# MocKhoaLedTraiTim.net
KiCad netlist of a schematic drawn in Altium Designer
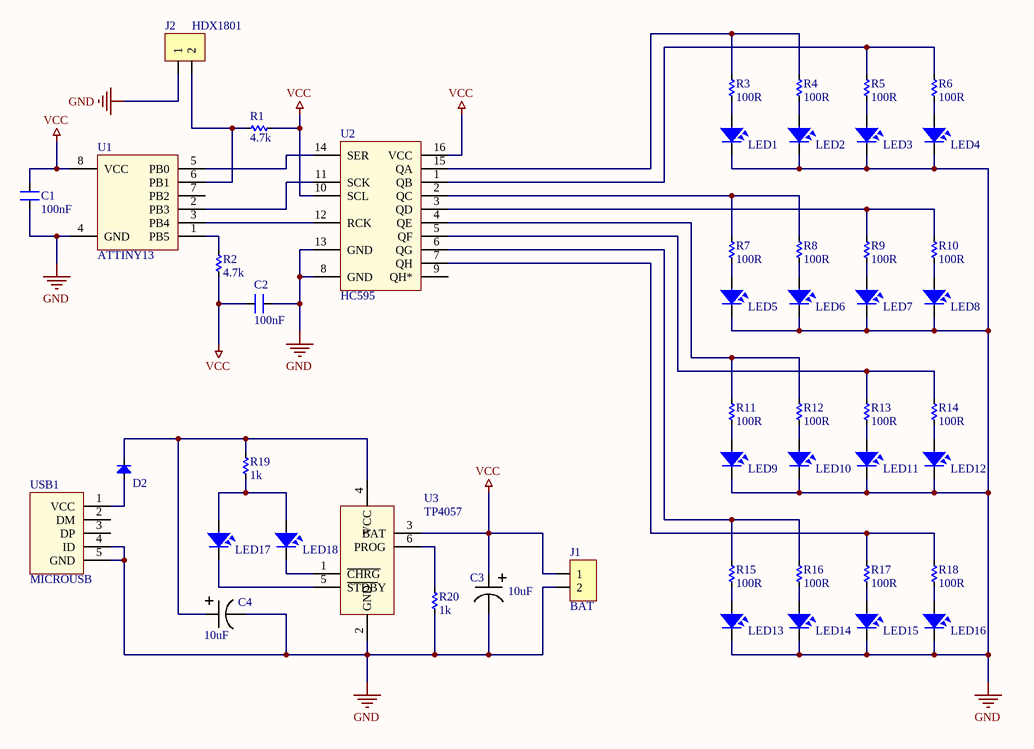
[diagram p0: MocKhoaLedTraiTim.SchDoc]

(export (version "E")
  (design (tool "Eeschema 10.0.6"))
  (components
    (comp (ref "C1") (value "100nF") (footprint "CN-SMD-0805") (libsource (lib "LIBRARY") (part "CN")))
    (comp (ref "C2") (value "100nF") (footprint "CN-SMD-0805") (libsource (lib "LIBRARY") (part "CN")))
    (comp (ref "C3") (value "10uF") (footprint "CAP1411") (libsource (lib "User") (part "CAP-TANTALUM")))
    (comp (ref "C4") (value "10uF") (footprint "CAP1411") (libsource (lib "") (part "CAP-TANTALUM_1")))
    (comp (ref "D2")
      (value "Diode SMD")
      (footprint "DIO-SMD-123")
      (description "Default Diode")
      (fields (field (name "PUBLISHER") "Altium Limited"))
      (libsource (lib "LIBRARY") (part "Diode SMD"))
    )
    (comp (ref "J1")
      (value "BAT")
      (footprint "JP2-D1T")
      (description "WR-PHD 2.54 mm Angled Socket Header")
      (fields
        (field (name "MANUFACTURER") "Würth Elektronik eiSos GmbH")
        (field (name "PARTNO") "613002143121")
        (field (name "CREATED BY") "Karrer Zheng")
      )
      (libsource (lib "LIBRARY") (part "JP2"))
    )
    (comp (ref "J2")
      (value "HDX1801")
      (footprint "JP2-D1T")
      (description "WR-PHD 2.54 mm Angled Socket Header")
      (fields
        (field (name "MANUFACTURER") "Würth Elektronik eiSos GmbH")
        (field (name "PARTNO") "613002143121")
        (field (name "CREATED BY") "Karrer Zheng")
      )
      (libsource (lib "") (part "JP2_1"))
    )
    (comp (ref "LED1")
      (value "LED")
      (footprint "LED-1206-Yellow")
      (libsource (lib "LIBRARY") (part "LED SMD"))
    )
    (comp (ref "LED2")
      (value "LED")
      (footprint "LED-1206-Yellow")
      (libsource (lib "LIBRARY") (part "LED SMD"))
    )
    (comp (ref "LED3")
      (value "LED")
      (footprint "LED-1206-Yellow")
      (libsource (lib "LIBRARY") (part "LED SMD"))
    )
    (comp (ref "LED4")
      (value "LED")
      (footprint "LED-1206-Yellow")
      (libsource (lib "LIBRARY") (part "LED SMD"))
    )
    (comp (ref "LED5")
      (value "LED")
      (footprint "LED-1206-Yellow")
      (libsource (lib "LIBRARY") (part "LED SMD"))
    )
    (comp (ref "LED6")
      (value "LED")
      (footprint "LED-1206-Yellow")
      (libsource (lib "LIBRARY") (part "LED SMD"))
    )
    (comp (ref "LED7")
      (value "LED")
      (footprint "LED-1206-Yellow")
      (libsource (lib "LIBRARY") (part "LED SMD"))
    )
    (comp (ref "LED8")
      (value "LED")
      (footprint "LED-1206-Yellow")
      (libsource (lib "LIBRARY") (part "LED SMD"))
    )
    (comp (ref "LED9")
      (value "LED")
      (footprint "LED-1206-Yellow")
      (libsource (lib "LIBRARY") (part "LED SMD"))
    )
    (comp (ref "LED10")
      (value "LED")
      (footprint "LED-1206-Yellow")
      (libsource (lib "LIBRARY") (part "LED SMD"))
    )
    (comp (ref "LED11")
      (value "LED")
      (footprint "LED-1206-Yellow")
      (libsource (lib "LIBRARY") (part "LED SMD"))
    )
    (comp (ref "LED12")
      (value "LED")
      (footprint "LED-1206-Yellow")
      (libsource (lib "LIBRARY") (part "LED SMD"))
    )
    (comp (ref "LED13")
      (value "LED")
      (footprint "LED-1206-Yellow")
      (libsource (lib "LIBRARY") (part "LED SMD"))
    )
    (comp (ref "LED14")
      (value "LED")
      (footprint "LED-1206-Yellow")
      (libsource (lib "LIBRARY") (part "LED SMD"))
    )
    (comp (ref "LED15")
      (value "LED")
      (footprint "LED-1206-Yellow")
      (libsource (lib "LIBRARY") (part "LED SMD"))
    )
    (comp (ref "LED16")
      (value "LED")
      (footprint "LED-1206-Yellow")
      (libsource (lib "LIBRARY") (part "LED SMD"))
    )
    (comp (ref "LED17")
      (value "LED")
      (footprint "LED-0805-Yellow")
      (libsource (lib "LIBRARY") (part "LED SMD"))
    )
    (comp (ref "LED18")
      (value "LED")
      (footprint "LED-0805-Yellow")
      (libsource (lib "LIBRARY") (part "LED SMD"))
    )
    (comp (ref "R1")
      (value "4.7k")
      (footprint "RES-SMD-0805")
      (description "Resistor")
      (fields
        (field (name "MANUFACTURER") "Generic Components")
        (field (name "PUBLISHER") "Altium Hobart Technology Centre")
      )
      (libsource (lib "LIBRARY") (part "Res-SMD"))
    )
    (comp (ref "R2")
      (value "4.7k")
      (footprint "RES-SMD-0805")
      (description "Resistor")
      (fields
        (field (name "MANUFACTURER") "Generic Components")
        (field (name "PUBLISHER") "Altium Hobart Technology Centre")
      )
      (libsource (lib "LIBRARY") (part "Res-SMD"))
    )
    (comp (ref "R3")
      (value "100R")
      (footprint "RES-SMD-0805")
      (description "Resistor")
      (fields
        (field (name "MANUFACTURER") "Generic Components")
        (field (name "PUBLISHER") "Altium Hobart Technology Centre")
      )
      (libsource (lib "LIBRARY") (part "Res-SMD"))
    )
    (comp (ref "R4")
      (value "100R")
      (footprint "RES-SMD-0805")
      (description "Resistor")
      (fields
        (field (name "MANUFACTURER") "Generic Components")
        (field (name "PUBLISHER") "Altium Hobart Technology Centre")
      )
      (libsource (lib "LIBRARY") (part "Res-SMD"))
    )
    (comp (ref "R5")
      (value "100R")
      (footprint "RES-SMD-0805")
      (description "Resistor")
      (fields
        (field (name "MANUFACTURER") "Generic Components")
        (field (name "PUBLISHER") "Altium Hobart Technology Centre")
      )
      (libsource (lib "LIBRARY") (part "Res-SMD"))
    )
    (comp (ref "R6")
      (value "100R")
      (footprint "RES-SMD-0805")
      (description "Resistor")
      (fields
        (field (name "MANUFACTURER") "Generic Components")
        (field (name "PUBLISHER") "Altium Hobart Technology Centre")
      )
      (libsource (lib "LIBRARY") (part "Res-SMD"))
    )
    (comp (ref "R7")
      (value "100R")
      (footprint "RES-SMD-0805")
      (description "Resistor")
      (fields
        (field (name "MANUFACTURER") "Generic Components")
        (field (name "PUBLISHER") "Altium Hobart Technology Centre")
      )
      (libsource (lib "LIBRARY") (part "Res-SMD"))
    )
    (comp (ref "R8")
      (value "100R")
      (footprint "RES-SMD-0805")
      (description "Resistor")
      (fields
        (field (name "MANUFACTURER") "Generic Components")
        (field (name "PUBLISHER") "Altium Hobart Technology Centre")
      )
      (libsource (lib "LIBRARY") (part "Res-SMD"))
    )
    (comp (ref "R9")
      (value "100R")
      (footprint "RES-SMD-0805")
      (description "Resistor")
      (fields
        (field (name "MANUFACTURER") "Generic Components")
        (field (name "PUBLISHER") "Altium Hobart Technology Centre")
      )
      (libsource (lib "LIBRARY") (part "Res-SMD"))
    )
    (comp (ref "R10")
      (value "100R")
      (footprint "RES-SMD-0805")
      (description "Resistor")
      (fields
        (field (name "MANUFACTURER") "Generic Components")
        (field (name "PUBLISHER") "Altium Hobart Technology Centre")
      )
      (libsource (lib "LIBRARY") (part "Res-SMD"))
    )
    (comp (ref "R11")
      (value "100R")
      (footprint "RES-SMD-0805")
      (description "Resistor")
      (fields
        (field (name "MANUFACTURER") "Generic Components")
        (field (name "PUBLISHER") "Altium Hobart Technology Centre")
      )
      (libsource (lib "LIBRARY") (part "Res-SMD"))
    )
    (comp (ref "R12")
      (value "100R")
      (footprint "RES-SMD-0805")
      (description "Resistor")
      (fields
        (field (name "MANUFACTURER") "Generic Components")
        (field (name "PUBLISHER") "Altium Hobart Technology Centre")
      )
      (libsource (lib "LIBRARY") (part "Res-SMD"))
    )
    (comp (ref "R13")
      (value "100R")
      (footprint "RES-SMD-0805")
      (description "Resistor")
      (fields
        (field (name "MANUFACTURER") "Generic Components")
        (field (name "PUBLISHER") "Altium Hobart Technology Centre")
      )
      (libsource (lib "LIBRARY") (part "Res-SMD"))
    )
    (comp (ref "R14")
      (value "100R")
      (footprint "RES-SMD-0805")
      (description "Resistor")
      (fields
        (field (name "MANUFACTURER") "Generic Components")
        (field (name "PUBLISHER") "Altium Hobart Technology Centre")
      )
      (libsource (lib "LIBRARY") (part "Res-SMD"))
    )
    (comp (ref "R15")
      (value "100R")
      (footprint "RES-SMD-0805")
      (description "Resistor")
      (fields
        (field (name "MANUFACTURER") "Generic Components")
        (field (name "PUBLISHER") "Altium Hobart Technology Centre")
      )
      (libsource (lib "LIBRARY") (part "Res-SMD"))
    )
    (comp (ref "R16")
      (value "100R")
      (footprint "RES-SMD-0805")
      (description "Resistor")
      (fields
        (field (name "MANUFACTURER") "Generic Components")
        (field (name "PUBLISHER") "Altium Hobart Technology Centre")
      )
      (libsource (lib "LIBRARY") (part "Res-SMD"))
    )
    (comp (ref "R17")
      (value "100R")
      (footprint "RES-SMD-0805")
      (description "Resistor")
      (fields
        (field (name "MANUFACTURER") "Generic Components")
        (field (name "PUBLISHER") "Altium Hobart Technology Centre")
      )
      (libsource (lib "LIBRARY") (part "Res-SMD"))
    )
    (comp (ref "R18")
      (value "100R")
      (footprint "RES-SMD-0805")
      (description "Resistor")
      (fields
        (field (name "MANUFACTURER") "Generic Components")
        (field (name "PUBLISHER") "Altium Hobart Technology Centre")
      )
      (libsource (lib "LIBRARY") (part "Res-SMD"))
    )
    (comp (ref "R19")
      (value "1k")
      (footprint "RES-SMD-0805")
      (description "Resistor")
      (fields
        (field (name "MANUFACTURER") "Generic Components")
        (field (name "PUBLISHER") "Altium Hobart Technology Centre")
      )
      (libsource (lib "LIBRARY") (part "Res-SMD"))
    )
    (comp (ref "R20")
      (value "1k")
      (footprint "RES-SMD-0805")
      (description "Resistor")
      (fields
        (field (name "MANUFACTURER") "Generic Components")
        (field (name "PUBLISHER") "Altium Hobart Technology Centre")
      )
      (libsource (lib "LIBRARY") (part "Res-SMD"))
    )
    (comp (ref "U1") (value "ATTINY13") (footprint "TINY13") (libsource (lib "User") (part "TINY13")))
    (comp (ref "U2") (value "HC595") (footprint "SOP16") (libsource (lib "User") (part "HC595")))
    (comp (ref "U3") (value "TP4057") (footprint "SOT23-6") (libsource (lib "User") (part "TP4057")))
    (comp (ref "USB1") (value "MICROUSB") (footprint "MICROUSB") (libsource (lib "User") (part "MICROUSB")))
  )
  (nets
    (net (code "1") (name "GND") (class "Default")
      (node (ref "C1") (pin "1") (pinfunction "1_1") (pintype "passive"))
      (node (ref "C2") (pin "1") (pinfunction "1_1") (pintype "passive"))
      (node (ref "C3") (pin "2") (pinfunction "2_2") (pintype "passive"))
      (node (ref "C4") (pin "2") (pinfunction "2_2") (pintype "passive"))
      (node (ref "J1") (pin "2") (pinfunction "2_2") (pintype "passive"))
      (node (ref "J2") (pin "1") (pinfunction "1_1") (pintype "passive"))
      (node (ref "LED1") (pin "2") (pinfunction "2_2") (pintype "passive"))
      (node (ref "LED10") (pin "2") (pinfunction "2_2") (pintype "passive"))
      (node (ref "LED11") (pin "2") (pinfunction "2_2") (pintype "passive"))
      (node (ref "LED12") (pin "2") (pinfunction "2_2") (pintype "passive"))
      (node (ref "LED13") (pin "2") (pinfunction "2_2") (pintype "passive"))
      (node (ref "LED14") (pin "2") (pinfunction "2_2") (pintype "passive"))
      (node (ref "LED15") (pin "2") (pinfunction "2_2") (pintype "passive"))
      (node (ref "LED16") (pin "2") (pinfunction "2_2") (pintype "passive"))
      (node (ref "LED2") (pin "2") (pinfunction "2_2") (pintype "passive"))
      (node (ref "LED3") (pin "2") (pinfunction "2_2") (pintype "passive"))
      (node (ref "LED4") (pin "2") (pinfunction "2_2") (pintype "passive"))
      (node (ref "LED5") (pin "2") (pinfunction "2_2") (pintype "passive"))
      (node (ref "LED6") (pin "2") (pinfunction "2_2") (pintype "passive"))
      (node (ref "LED7") (pin "2") (pinfunction "2_2") (pintype "passive"))
      (node (ref "LED8") (pin "2") (pinfunction "2_2") (pintype "passive"))
      (node (ref "LED9") (pin "2") (pinfunction "2_2") (pintype "passive"))
      (node (ref "R20") (pin "1") (pinfunction "1_1") (pintype "passive"))
      (node (ref "U1") (pin "4") (pinfunction "GND_4") (pintype "passive"))
      (node (ref "U2") (pin "13") (pinfunction "GND_13") (pintype "passive"))
      (node (ref "U2") (pin "8") (pinfunction "GND_8") (pintype "passive"))
      (node (ref "U3") (pin "2") (pinfunction "GND_2") (pintype "passive"))
      (node (ref "USB1") (pin "4") (pinfunction "ID_4") (pintype "passive"))
      (node (ref "USB1") (pin "5") (pinfunction "GND_5") (pintype "passive"))
    )
    (net (code "2") (name "Net-(D2-A)") (class "Default")
      (node (ref "D2") (pin "1") (pinfunction "A_1") (pintype "passive"))
      (node (ref "USB1") (pin "1") (pinfunction "VCC_1") (pintype "passive"))
    )
    (net (code "3") (name "Net-(D2-K)") (class "Default")
      (node (ref "C4") (pin "1") (pinfunction "1_1") (pintype "passive"))
      (node (ref "D2") (pin "2") (pinfunction "K_2") (pintype "passive"))
      (node (ref "R19") (pin "2") (pinfunction "2_2") (pintype "passive"))
      (node (ref "U3") (pin "4") (pinfunction "VCC_4") (pintype "passive"))
    )
    (net (code "4") (name "Net-(LED1-Pad1)") (class "Default")
      (node (ref "LED1") (pin "1") (pinfunction "1_1") (pintype "passive"))
      (node (ref "R3") (pin "1") (pinfunction "1_1") (pintype "passive"))
    )
    (net (code "5") (name "Net-(LED2-Pad1)") (class "Default")
      (node (ref "LED2") (pin "1") (pinfunction "1_1") (pintype "passive"))
      (node (ref "R4") (pin "1") (pinfunction "1_1") (pintype "passive"))
    )
    (net (code "6") (name "Net-(LED3-Pad1)") (class "Default")
      (node (ref "LED3") (pin "1") (pinfunction "1_1") (pintype "passive"))
      (node (ref "R5") (pin "1") (pinfunction "1_1") (pintype "passive"))
    )
    (net (code "7") (name "Net-(LED4-Pad1)") (class "Default")
      (node (ref "LED4") (pin "1") (pinfunction "1_1") (pintype "passive"))
      (node (ref "R6") (pin "1") (pinfunction "1_1") (pintype "passive"))
    )
    (net (code "8") (name "Net-(LED5-Pad1)") (class "Default")
      (node (ref "LED5") (pin "1") (pinfunction "1_1") (pintype "passive"))
      (node (ref "R7") (pin "1") (pinfunction "1_1") (pintype "passive"))
    )
    (net (code "9") (name "Net-(LED6-Pad1)") (class "Default")
      (node (ref "LED6") (pin "1") (pinfunction "1_1") (pintype "passive"))
      (node (ref "R8") (pin "1") (pinfunction "1_1") (pintype "passive"))
    )
    (net (code "10") (name "Net-(LED7-Pad1)") (class "Default")
      (node (ref "LED7") (pin "1") (pinfunction "1_1") (pintype "passive"))
      (node (ref "R9") (pin "1") (pinfunction "1_1") (pintype "passive"))
    )
    (net (code "11") (name "Net-(LED8-Pad1)") (class "Default")
      (node (ref "LED8") (pin "1") (pinfunction "1_1") (pintype "passive"))
      (node (ref "R10") (pin "1") (pinfunction "1_1") (pintype "passive"))
    )
    (net (code "12") (name "Net-(LED9-Pad1)") (class "Default")
      (node (ref "LED9") (pin "1") (pinfunction "1_1") (pintype "passive"))
      (node (ref "R11") (pin "1") (pinfunction "1_1") (pintype "passive"))
    )
    (net (code "13") (name "Net-(LED10-Pad1)") (class "Default")
      (node (ref "LED10") (pin "1") (pinfunction "1_1") (pintype "passive"))
      (node (ref "R12") (pin "1") (pinfunction "1_1") (pintype "passive"))
    )
    (net (code "14") (name "Net-(LED11-Pad1)") (class "Default")
      (node (ref "LED11") (pin "1") (pinfunction "1_1") (pintype "passive"))
      (node (ref "R13") (pin "1") (pinfunction "1_1") (pintype "passive"))
    )
    (net (code "15") (name "Net-(LED12-Pad1)") (class "Default")
      (node (ref "LED12") (pin "1") (pinfunction "1_1") (pintype "passive"))
      (node (ref "R14") (pin "1") (pinfunction "1_1") (pintype "passive"))
    )
    (net (code "16") (name "Net-(LED13-Pad1)") (class "Default")
      (node (ref "LED13") (pin "1") (pinfunction "1_1") (pintype "passive"))
      (node (ref "R15") (pin "1") (pinfunction "1_1") (pintype "passive"))
    )
    (net (code "17") (name "Net-(LED14-Pad1)") (class "Default")
      (node (ref "LED14") (pin "1") (pinfunction "1_1") (pintype "passive"))
      (node (ref "R16") (pin "1") (pinfunction "1_1") (pintype "passive"))
    )
    (net (code "18") (name "Net-(LED15-Pad1)") (class "Default")
      (node (ref "LED15") (pin "1") (pinfunction "1_1") (pintype "passive"))
      (node (ref "R17") (pin "1") (pinfunction "1_1") (pintype "passive"))
    )
    (net (code "19") (name "Net-(LED16-Pad1)") (class "Default")
      (node (ref "LED16") (pin "1") (pinfunction "1_1") (pintype "passive"))
      (node (ref "R18") (pin "1") (pinfunction "1_1") (pintype "passive"))
    )
    (net (code "20") (name "Net-(LED17-Pad1)") (class "Default")
      (node (ref "LED17") (pin "1") (pinfunction "1_1") (pintype "passive"))
      (node (ref "LED18") (pin "1") (pinfunction "1_1") (pintype "passive"))
      (node (ref "R19") (pin "1") (pinfunction "1_1") (pintype "passive"))
    )
    (net (code "21") (name "Net-(U1-PB0)") (class "Default")
      (node (ref "U1") (pin "5") (pinfunction "PB0_5") (pintype "passive"))
      (node (ref "U2") (pin "14") (pinfunction "SER_14") (pintype "passive"))
    )
    (net (code "22") (name "Net-(U1-PB1)") (class "Default")
      (node (ref "J2") (pin "2") (pinfunction "2_2") (pintype "passive"))
      (node (ref "R1") (pin "1") (pinfunction "1_1") (pintype "passive"))
      (node (ref "U1") (pin "6") (pinfunction "PB1_6") (pintype "passive"))
    )
    (net (code "23") (name "Net-(U1-PB3)") (class "Default")
      (node (ref "U1") (pin "2") (pinfunction "PB3_2") (pintype "passive"))
      (node (ref "U2") (pin "11") (pinfunction "SCK_11") (pintype "passive"))
    )
    (net (code "24") (name "Net-(U1-PB4)") (class "Default")
      (node (ref "U1") (pin "3") (pinfunction "PB4_3") (pintype "passive"))
      (node (ref "U2") (pin "12") (pinfunction "RCK_12") (pintype "passive"))
    )
    (net (code "25") (name "Net-(U1-PB5)") (class "Default")
      (node (ref "R2") (pin "1") (pinfunction "1_1") (pintype "passive"))
      (node (ref "U1") (pin "1") (pinfunction "PB5_1") (pintype "passive"))
    )
    (net (code "26") (name "Net-(U2-QA)") (class "Default")
      (node (ref "R3") (pin "2") (pinfunction "2_2") (pintype "passive"))
      (node (ref "R4") (pin "2") (pinfunction "2_2") (pintype "passive"))
      (node (ref "U2") (pin "15") (pinfunction "QA_15") (pintype "passive"))
    )
    (net (code "27") (name "Net-(U2-QB)") (class "Default")
      (node (ref "R5") (pin "2") (pinfunction "2_2") (pintype "passive"))
      (node (ref "R6") (pin "2") (pinfunction "2_2") (pintype "passive"))
      (node (ref "U2") (pin "1") (pinfunction "QB_1") (pintype "passive"))
    )
    (net (code "28") (name "Net-(U2-QC)") (class "Default")
      (node (ref "R7") (pin "2") (pinfunction "2_2") (pintype "passive"))
      (node (ref "R8") (pin "2") (pinfunction "2_2") (pintype "passive"))
      (node (ref "U2") (pin "2") (pinfunction "QC_2") (pintype "passive"))
    )
    (net (code "29") (name "Net-(U2-QD)") (class "Default")
      (node (ref "R10") (pin "2") (pinfunction "2_2") (pintype "passive"))
      (node (ref "R9") (pin "2") (pinfunction "2_2") (pintype "passive"))
      (node (ref "U2") (pin "3") (pinfunction "QD_3") (pintype "passive"))
    )
    (net (code "30") (name "Net-(U2-QE)") (class "Default")
      (node (ref "R11") (pin "2") (pinfunction "2_2") (pintype "passive"))
      (node (ref "R12") (pin "2") (pinfunction "2_2") (pintype "passive"))
      (node (ref "U2") (pin "4") (pinfunction "QE_4") (pintype "passive"))
    )
    (net (code "31") (name "Net-(U2-QF)") (class "Default")
      (node (ref "R13") (pin "2") (pinfunction "2_2") (pintype "passive"))
      (node (ref "R14") (pin "2") (pinfunction "2_2") (pintype "passive"))
      (node (ref "U2") (pin "5") (pinfunction "QF_5") (pintype "passive"))
    )
    (net (code "32") (name "Net-(U2-QG)") (class "Default")
      (node (ref "R15") (pin "2") (pinfunction "2_2") (pintype "passive"))
      (node (ref "R16") (pin "2") (pinfunction "2_2") (pintype "passive"))
      (node (ref "U2") (pin "6") (pinfunction "QG_6") (pintype "passive"))
    )
    (net (code "33") (name "Net-(U2-QH)") (class "Default")
      (node (ref "R17") (pin "2") (pinfunction "2_2") (pintype "passive"))
      (node (ref "R18") (pin "2") (pinfunction "2_2") (pintype "passive"))
      (node (ref "U2") (pin "7") (pinfunction "QH_7") (pintype "passive"))
    )
    (net (code "34") (name "Net-(U3-PROG)") (class "Default")
      (node (ref "R20") (pin "2") (pinfunction "2_2") (pintype "passive"))
      (node (ref "U3") (pin "6") (pinfunction "PROG_6") (pintype "passive"))
    )
    (net (code "35") (name "Net-(U3-~{CHRG})") (class "Default")
      (node (ref "LED18") (pin "2") (pinfunction "2_2") (pintype "passive"))
      (node (ref "U3") (pin "1") (pinfunction "~{CHRG}_1") (pintype "passive"))
    )
    (net (code "36") (name "Net-(U3-~{STDB}Y)") (class "Default")
      (node (ref "LED17") (pin "2") (pinfunction "2_2") (pintype "passive"))
      (node (ref "U3") (pin "5") (pinfunction "~{STDB}Y_5") (pintype "passive"))
    )
    (net (code "37") (name "VCC") (class "Default")
      (node (ref "C1") (pin "2") (pinfunction "2_2") (pintype "passive"))
      (node (ref "C2") (pin "2") (pinfunction "2_2") (pintype "passive"))
      (node (ref "C3") (pin "1") (pinfunction "1_1") (pintype "passive"))
      (node (ref "J1") (pin "1") (pinfunction "1_1") (pintype "passive"))
      (node (ref "R1") (pin "2") (pinfunction "2_2") (pintype "passive"))
      (node (ref "R2") (pin "2") (pinfunction "2_2") (pintype "passive"))
      (node (ref "U1") (pin "8") (pinfunction "VCC_8") (pintype "passive"))
      (node (ref "U2") (pin "10") (pinfunction "SCL_10") (pintype "passive"))
      (node (ref "U2") (pin "16") (pinfunction "VCC_16") (pintype "passive"))
      (node (ref "U3") (pin "3") (pinfunction "BAT_3") (pintype "passive"))
    )
    (net (code "38") (name "unconnected-(U1-PB2-Pad7)") (class "Default")
      (node (ref "U1") (pin "7") (pinfunction "PB2_7") (pintype "passive"))
    )
    (net (code "39") (name "unconnected-(U2-QH*-Pad9)") (class "Default")
      (node (ref "U2") (pin "9") (pinfunction "QH*_9") (pintype "passive"))
    )
    (net (code "40") (name "unconnected-(USB1-DM-Pad2)") (class "Default")
      (node (ref "USB1") (pin "2") (pinfunction "DM_2") (pintype "passive"))
    )
    (net (code "41") (name "unconnected-(USB1-DP-Pad3)") (class "Default")
      (node (ref "USB1") (pin "3") (pinfunction "DP_3") (pintype "passive"))
    )
  )
)
